# CAN.net
KiCad netlist of a schematic drawn in Altium Designer
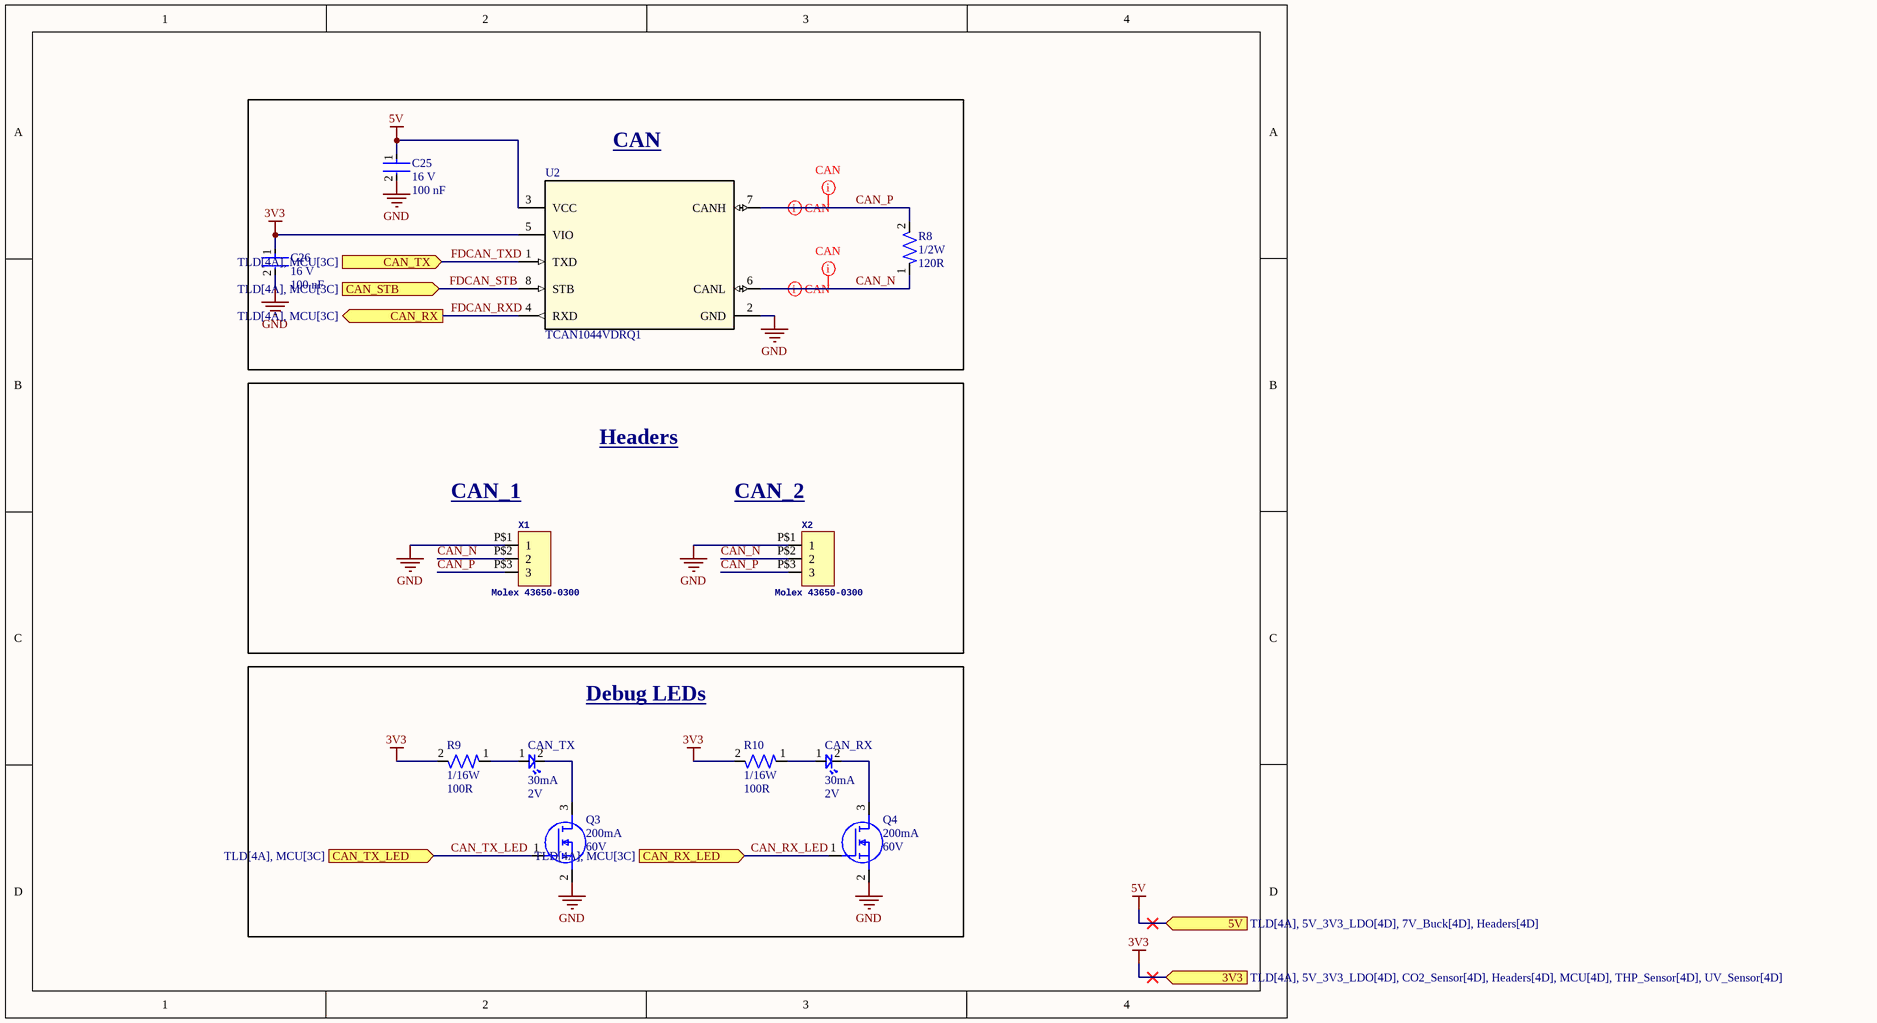
[diagram p0: CAN.SchDoc]

(export (version "E")
  (design (tool "Eeschema 10.0.6"))
  (components
    (comp (ref "C25")
      (value "CC0402KRX7R7BB104")
      (footprint "CAP-0402")
      (description "CAP CER 0.1UF 16V X7R 0402")
      (fields (field (name "VOLTAGE RATING") "16 V") (field (name "CAPACITANCE") "100 nF"))
      (libsource (lib "JLC_25") (part "CAP-0.1U-0001"))
    )
    (comp (ref "C26")
      (value "CC0402KRX7R7BB104")
      (footprint "CAP-0402")
      (description "CAP CER 0.1UF 16V X7R 0402")
      (fields (field (name "VOLTAGE RATING") "16 V") (field (name "CAPACITANCE") "100 nF"))
      (libsource (lib "JLC_25") (part "CAP-0.1U-0001"))
    )
    (comp (ref "CAN_RX")
      (value "BL-HKC36G-AV-TRB")
      (footprint "LED-0603")
      (description "LED YELLOW CLEAR 0603 SMD")
      (fields (field (name "FORWARD CURRENT") "30mA") (field (name "FORWARD VOLTAGE") "2V"))
      (libsource (lib "JLC_25") (part "LED-0001"))
    )
    (comp (ref "CAN_TX")
      (value "BL-HKC36G-AV-TRB")
      (footprint "LED-0603")
      (description "LED YELLOW CLEAR 0603 SMD")
      (fields (field (name "FORWARD CURRENT") "30mA") (field (name "FORWARD VOLTAGE") "2V"))
      (libsource (lib "JLC_25") (part "LED-0001"))
    )
    (comp (ref "Q3")
      (value "T2N7002AK,LM")
      (footprint "IC-SOT23-3")
      (description "MOSFET N-CH 60V 200MA SOT23")
      (fields (field (name "CONTINUOUS CURRENT") "200mA") (field (name "VOLTAGE") "60V"))
      (libsource (lib "JLC_25") (part "NMOS-200MA-0001"))
    )
    (comp (ref "Q4")
      (value "T2N7002AK,LM")
      (footprint "IC-SOT23-3")
      (description "MOSFET N-CH 60V 200MA SOT23")
      (fields (field (name "CONTINUOUS CURRENT") "200mA") (field (name "VOLTAGE") "60V"))
      (libsource (lib "JLC_25") (part "NMOS-200MA-0001"))
    )
    (comp (ref "R8")
      (value "RC1210FR-07120RL")
      (footprint "RES-1210")
      (description "RES 120 OHM 1% 1/2W 1210")
      (fields
        (field (name "TOLERANCE") "1%")
        (field (name "POWER") "1/2W")
        (field (name "RESISTANCE") "120R")
      )
      (libsource (lib "JLC_25") (part "RES-120-0001"))
    )
    (comp (ref "R9")
      (value "RC0402FR-07100RL")
      (footprint "RES-0402")
      (description "RES 100 OHM 1% 1/16W 0402")
      (fields
        (field (name "TOLERANCE") "1%")
        (field (name "POWER") "1/16W")
        (field (name "RESISTANCE") "100R")
      )
      (libsource (lib "JLC_25") (part "RES-100-0001"))
    )
    (comp (ref "R10")
      (value "RC0402FR-07100RL")
      (footprint "RES-0402")
      (description "RES 100 OHM 1% 1/16W 0402")
      (fields
        (field (name "TOLERANCE") "1%")
        (field (name "POWER") "1/16W")
        (field (name "RESISTANCE") "100R")
      )
      (libsource (lib "JLC_25") (part "RES-100-0001"))
    )
    (comp (ref "U2")
      (value "TCAN1044VDRQ1")
      (footprint "IC-8SOIC")
      (description "IC TRANSCEIVER 1/1 8SOIC")
      (libsource (lib "JLC_25") (part "IC-CAN-0001"))
    )
    (comp (ref "X1")
      (value "Molex 43650-0300")
      (footprint "43650-0300")
      (libsource (lib "Molex Microfit") (part "Micro-Fit Molex 3 Pin Right Angle"))
    )
    (comp (ref "X2")
      (value "Molex 43650-0300")
      (footprint "43650-0300")
      (libsource (lib "Molex Microfit") (part "Micro-Fit Molex 3 Pin Right Angle"))
    )
  )
  (nets
    (net (code "1") (name "/CAN_N") (class "Default")
      (node (ref "R8") (pin "1") (pinfunction "1_1") (pintype "passive"))
      (node (ref "U2") (pin "6") (pinfunction "CANL_6") (pintype "bidirectional"))
      (node (ref "X1") (pin "P$2") (pinfunction "2_P$2") (pintype "passive"))
      (node (ref "X2") (pin "P$2") (pinfunction "2_P$2") (pintype "passive"))
    )
    (net (code "2") (name "/CAN_P") (class "Default")
      (node (ref "R8") (pin "2") (pinfunction "2_2") (pintype "passive"))
      (node (ref "U2") (pin "7") (pinfunction "CANH_7") (pintype "bidirectional"))
      (node (ref "X1") (pin "P$3") (pinfunction "3_P$3") (pintype "passive"))
      (node (ref "X2") (pin "P$3") (pinfunction "3_P$3") (pintype "passive"))
    )
    (net (code "3") (name "/CAN_RX_LED") (class "Default")
      (node (ref "Q4") (pin "1") (pinfunction "G_1") (pintype "passive"))
    )
    (net (code "4") (name "/CAN_TX_LED") (class "Default")
      (node (ref "Q3") (pin "1") (pinfunction "G_1") (pintype "passive"))
    )
    (net (code "5") (name "/FDCAN_RXD") (class "Default")
      (node (ref "U2") (pin "4") (pinfunction "RXD_4") (pintype "output"))
    )
    (net (code "6") (name "/FDCAN_STB") (class "Default")
      (node (ref "U2") (pin "8") (pinfunction "STB_8") (pintype "input"))
    )
    (net (code "7") (name "/FDCAN_TXD") (class "Default")
      (node (ref "U2") (pin "1") (pinfunction "TXD_1") (pintype "input"))
    )
    (net (code "8") (name "3V3") (class "Default")
      (node (ref "C26") (pin "1") (pinfunction "1_1") (pintype "passive"))
      (node (ref "R10") (pin "2") (pinfunction "2_2") (pintype "passive"))
      (node (ref "R9") (pin "2") (pinfunction "2_2") (pintype "passive"))
      (node (ref "U2") (pin "5") (pinfunction "VIO_5") (pintype "power_in"))
    )
    (net (code "9") (name "5V") (class "Default")
      (node (ref "C25") (pin "1") (pinfunction "1_1") (pintype "passive"))
      (node (ref "U2") (pin "3") (pinfunction "VCC_3") (pintype "power_in"))
    )
    (net (code "10") (name "GND") (class "Default")
      (node (ref "C25") (pin "2") (pinfunction "2_2") (pintype "passive"))
      (node (ref "C26") (pin "2") (pinfunction "2_2") (pintype "passive"))
      (node (ref "Q3") (pin "2") (pinfunction "S_2") (pintype "passive"))
      (node (ref "Q4") (pin "2") (pinfunction "S_2") (pintype "passive"))
      (node (ref "U2") (pin "2") (pinfunction "GND_2") (pintype "power_in"))
      (node (ref "X1") (pin "P$1") (pinfunction "1_P$1") (pintype "passive"))
      (node (ref "X2") (pin "P$1") (pinfunction "1_P$1") (pintype "passive"))
    )
    (net (code "11") (name "Net-(CAN_RX-Pad1)") (class "Default")
      (node (ref "CAN_RX") (pin "1") (pinfunction "1_1") (pintype "passive"))
      (node (ref "R10") (pin "1") (pinfunction "1_1") (pintype "passive"))
    )
    (net (code "12") (name "Net-(CAN_TX-Pad1)") (class "Default")
      (node (ref "CAN_TX") (pin "1") (pinfunction "1_1") (pintype "passive"))
      (node (ref "R9") (pin "1") (pinfunction "1_1") (pintype "passive"))
    )
    (net (code "13") (name "Net-(Q3-D)") (class "Default")
      (node (ref "CAN_TX") (pin "2") (pinfunction "2_2") (pintype "passive"))
      (node (ref "Q3") (pin "3") (pinfunction "D_3") (pintype "passive"))
    )
    (net (code "14") (name "Net-(Q4-D)") (class "Default")
      (node (ref "CAN_RX") (pin "2") (pinfunction "2_2") (pintype "passive"))
      (node (ref "Q4") (pin "3") (pinfunction "D_3") (pintype "passive"))
    )
  )
)
